# ADC_CH_B.net
KiCad netlist of a schematic drawn in Altium Designer
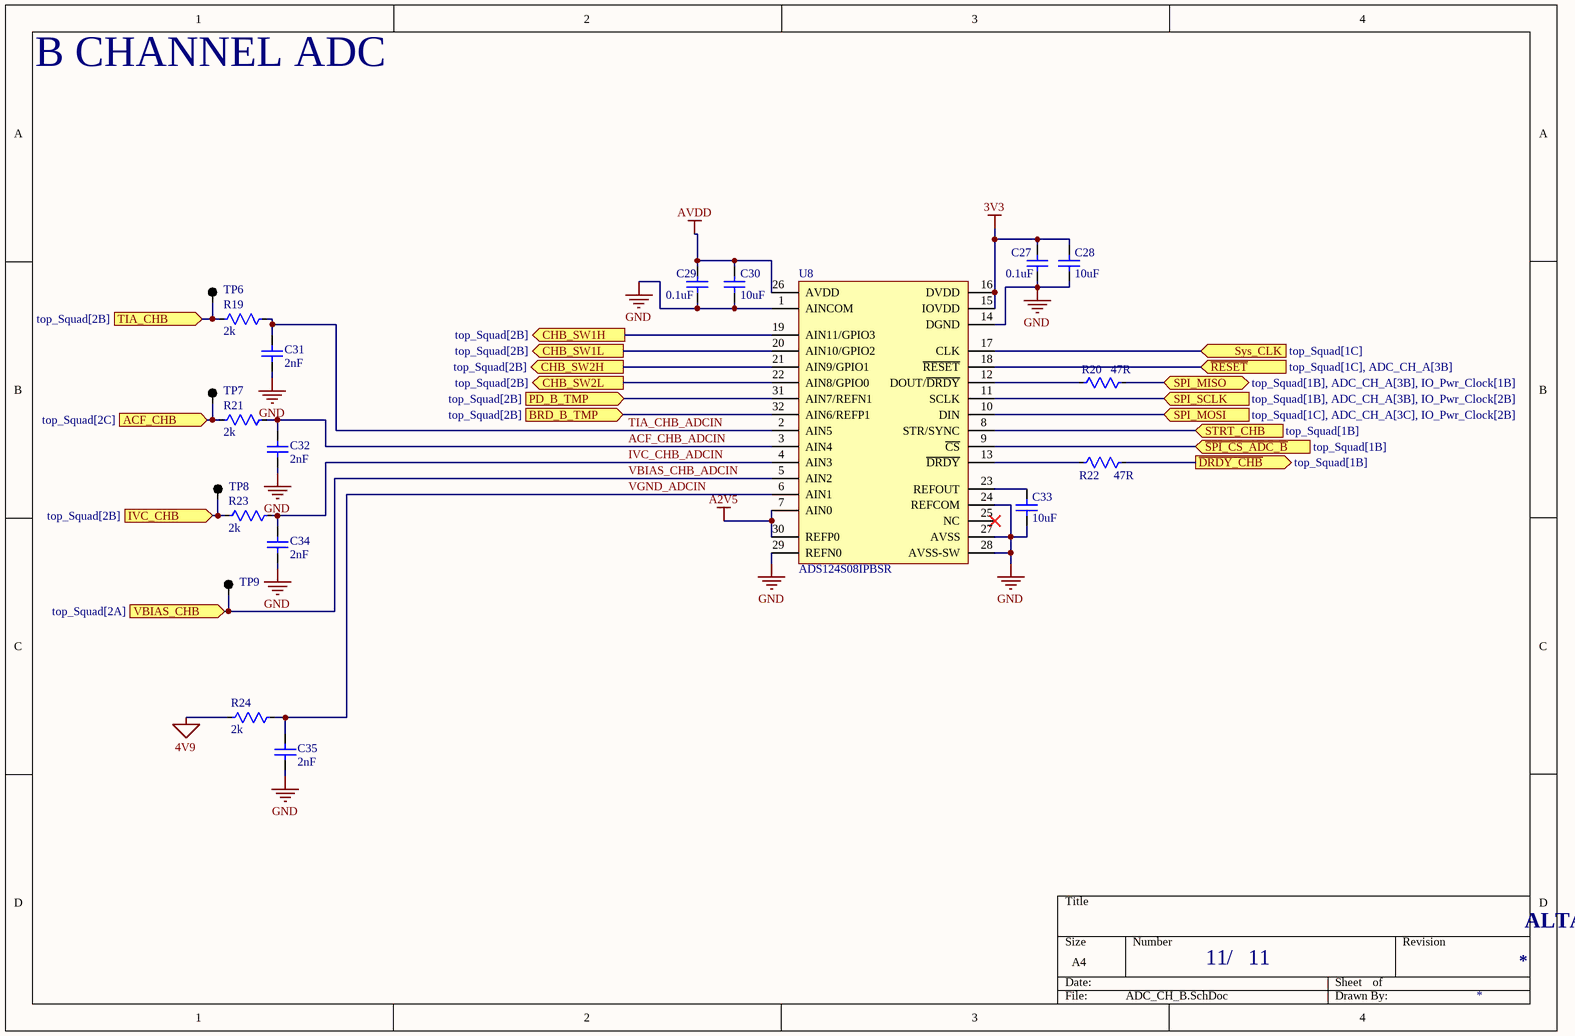
[diagram p0: ADC_CH_B.SchDoc]

(export (version "E")
  (design (tool "Eeschema 10.0.6"))
  (components
    (comp (ref "C27")
      (value "0.1uF")
      (footprint "CAP 0603 IPC MID DENSITY")
      (description "Kemet C0603C104K5RACAUTO - Cap Ceramic 0.1uF 50V X7R 10% 0603 125C Paper T/R")
      (fields (field (name "MF") "Kemet") (field (name "MP") "C0603C104K5RACAUTO"))
      (libsource (lib "ALTAIR_PD_Capacitors") (part "CAP"))
    )
    (comp (ref "C28")
      (value "10uF")
      (footprint "CAP 0805 IPC MID DENSITY")
      (description "Murata GRM21BR61E106KA73L - Cap Ceramic 10uF 10% 25V X5R 0805")
      (fields (field (name "MF") "Murata") (field (name "MP") "GRM21BR61E106KA73L"))
      (libsource (lib "ALTAIR_PD_Capacitors") (part "CAP"))
    )
    (comp (ref "C29")
      (value "0.1uF")
      (footprint "CAP 0603 IPC MID DENSITY")
      (description "Kemet C0603C104K5RACAUTO - Cap Ceramic 0.1uF 50V X7R 10% 0603 125C Paper T/R")
      (fields (field (name "MF") "Kemet") (field (name "MP") "C0603C104K5RACAUTO"))
      (libsource (lib "ALTAIR_PD_Capacitors") (part "CAP"))
    )
    (comp (ref "C30")
      (value "10uF")
      (footprint "CAP 0805 IPC MID DENSITY")
      (description "Murata GRM21BR61E106KA73L - Cap Ceramic 10uF 10% 25V X5R 0805")
      (fields (field (name "MF") "Murata") (field (name "MP") "GRM21BR61E106KA73L"))
      (libsource (lib "ALTAIR_PD_Capacitors") (part "CAP"))
    )
    (comp (ref "C31")
      (value "2nF")
      (footprint "CAP 0603 IPC MID DENSITY")
      (description "Murata GCM1885C1H202FA16J 50V 2nF C0G ±1% 0603")
      (fields (field (name "MF") "Murata") (field (name "MP") "GCM1885C1H202FA16J"))
      (libsource (lib "ALTAIR_PD_Capacitors") (part "CAP"))
    )
    (comp (ref "C32")
      (value "2nF")
      (footprint "CAP 0603 IPC MID DENSITY")
      (description "Murata GCM1885C1H202FA16J 50V 2nF C0G ±1% 0603")
      (fields (field (name "MF") "Murata") (field (name "MP") "GCM1885C1H202FA16J"))
      (libsource (lib "ALTAIR_PD_Capacitors") (part "CAP"))
    )
    (comp (ref "C33")
      (value "10uF")
      (footprint "CAP 0805 IPC MID DENSITY")
      (description "Murata GRM21BR61E106KA73L - Cap Ceramic 10uF 10% 25V X5R 0805")
      (fields (field (name "MF") "Murata") (field (name "MP") "GRM21BR61E106KA73L"))
      (libsource (lib "ALTAIR_PD_Capacitors") (part "CAP"))
    )
    (comp (ref "C34")
      (value "2nF")
      (footprint "CAP 0603 IPC MID DENSITY")
      (description "Murata GCM1885C1H202FA16J 50V 2nF C0G ±1% 0603")
      (fields (field (name "MF") "Murata") (field (name "MP") "GCM1885C1H202FA16J"))
      (libsource (lib "ALTAIR_PD_Capacitors") (part "CAP"))
    )
    (comp (ref "C35")
      (value "2nF")
      (footprint "CAP 0603 IPC MID DENSITY")
      (description "Murata GCM1885C1H202FA16J 50V 2nF C0G ±1% 0603")
      (fields (field (name "MF") "Murata") (field (name "MP") "GCM1885C1H202FA16J"))
      (libsource (lib "ALTAIR_PD_Capacitors") (part "CAP"))
    )
    (comp (ref "R19")
      (value "2k")
      (footprint "RES 0603 IPC MID DENSITY")
      (description "Panasonic ERJ-3EKF2001V Res Thick Film 0603 2K Ohm 1% 1/10W ±100ppm/°C")
      (fields (field (name "MF") "Panasonic Electronic Components") (field (name "MP") "ERJ-3EKF2001V"))
      (libsource (lib "ALTAIR_PD_Resistors") (part "RES"))
    )
    (comp (ref "R20")
      (value "47R")
      (footprint "RES 0402 NON-IPC SEI")
      (description "Stackpole RMCF0402JT47R0 - Res 47Ohm 5% 0.063W 0402 Thick Film AEC-Q200 compliant")
      (fields (field (name "MF") "Stackpole Electronics Inc.") (field (name "MP") "RMCF0402JT47R0"))
      (libsource (lib "ALTAIR_PD_Resistors") (part "RES"))
    )
    (comp (ref "R21")
      (value "2k")
      (footprint "RES 0603 IPC MID DENSITY")
      (description "Panasonic ERJ-3EKF2001V Res Thick Film 0603 2K Ohm 1% 1/10W ±100ppm/°C")
      (fields (field (name "MF") "Panasonic Electronic Components") (field (name "MP") "ERJ-3EKF2001V"))
      (libsource (lib "ALTAIR_PD_Resistors") (part "RES"))
    )
    (comp (ref "R22")
      (value "47R")
      (footprint "RES 0402 NON-IPC SEI")
      (description "Stackpole RMCF0402JT47R0 - Res 47Ohm 5% 0.063W 0402 Thick Film AEC-Q200 compliant")
      (fields (field (name "MF") "Stackpole Electronics Inc.") (field (name "MP") "RMCF0402JT47R0"))
      (libsource (lib "ALTAIR_PD_Resistors") (part "RES"))
    )
    (comp (ref "R23")
      (value "2k")
      (footprint "RES 0603 IPC MID DENSITY")
      (description "Panasonic ERJ-3EKF2001V Res Thick Film 0603 2K Ohm 1% 1/10W ±100ppm/°C")
      (fields (field (name "MF") "Panasonic Electronic Components") (field (name "MP") "ERJ-3EKF2001V"))
      (libsource (lib "ALTAIR_PD_Resistors") (part "RES"))
    )
    (comp (ref "R24")
      (value "2k")
      (footprint "RES 0603 IPC MID DENSITY")
      (description "Panasonic ERJ-3EKF2001V Res Thick Film 0603 2K Ohm 1% 1/10W ±100ppm/°C")
      (fields (field (name "MF") "Panasonic Electronic Components") (field (name "MP") "ERJ-3EKF2001V"))
      (libsource (lib "ALTAIR_PD_Resistors") (part "RES"))
    )
    (comp (ref "TP6")
      (value "Testpoint")
      (footprint "TESTPOINT THT")
      (libsource (lib "ALTAIR_PD_Testpoint") (part "Testpoint"))
    )
    (comp (ref "TP7")
      (value "Testpoint")
      (footprint "TESTPOINT THT")
      (libsource (lib "ALTAIR_PD_Testpoint") (part "Testpoint"))
    )
    (comp (ref "TP8")
      (value "Testpoint")
      (footprint "TESTPOINT THT")
      (libsource (lib "ALTAIR_PD_Testpoint") (part "Testpoint"))
    )
    (comp (ref "TP9")
      (value "Testpoint")
      (footprint "TESTPOINT THT")
      (libsource (lib "ALTAIR_PD_Testpoint") (part "Testpoint"))
    )
    (comp (ref "U8")
      (value "ADS124S08IPBSR")
      (footprint "32TQFP 7X7MM IPC LOW DENSITY")
      (description "24BIT ADC Delta-Sigma 4k samples/s PGA V-reference")
      (fields (field (name "MF") "Texas Instruments"))
      (libsource (lib "ALTAIR_PD_ADCs") (part "ADS124S08IPBSR"))
    )
  )
  (nets
    (net (code "1") (name "/ACF_CHB") (class "Default")
      (node (ref "R21") (pin "1") (pinfunction "1_1") (pintype "passive"))
      (node (ref "TP7") (pin "1") (pinfunction "1_1") (pintype "passive"))
    )
    (net (code "2") (name "/ACF_CHB_ADCIN") (class "Default")
      (node (ref "C32") (pin "2") (pinfunction "2_2") (pintype "passive"))
      (node (ref "R21") (pin "2") (pinfunction "2_2") (pintype "passive"))
      (node (ref "U8") (pin "3") (pinfunction "AIN4_3") (pintype "passive"))
    )
    (net (code "3") (name "/BRD_B_TMP") (class "Default")
      (node (ref "U8") (pin "32") (pinfunction "AIN6/REFP1_32") (pintype "passive"))
    )
    (net (code "4") (name "/CHB_SW1H") (class "Default")
      (node (ref "U8") (pin "19") (pinfunction "AIN11/GPIO3_19") (pintype "passive"))
    )
    (net (code "5") (name "/CHB_SW1L") (class "Default")
      (node (ref "U8") (pin "20") (pinfunction "AIN10/GPIO2_20") (pintype "passive"))
    )
    (net (code "6") (name "/CHB_SW2H") (class "Default")
      (node (ref "U8") (pin "21") (pinfunction "AIN9/GPIO1_21") (pintype "passive"))
    )
    (net (code "7") (name "/CHB_SW2L") (class "Default")
      (node (ref "U8") (pin "22") (pinfunction "AIN8/GPIO0_22") (pintype "passive"))
    )
    (net (code "8") (name "/DRDY_CHB") (class "Default")
      (node (ref "R22") (pin "2") (pinfunction "2_2") (pintype "passive"))
    )
    (net (code "9") (name "/IVC_CHB") (class "Default")
      (node (ref "R23") (pin "1") (pinfunction "1_1") (pintype "passive"))
      (node (ref "TP8") (pin "1") (pinfunction "1_1") (pintype "passive"))
    )
    (net (code "10") (name "/IVC_CHB_ADCIN") (class "Default")
      (node (ref "C34") (pin "2") (pinfunction "2_2") (pintype "passive"))
      (node (ref "R23") (pin "2") (pinfunction "2_2") (pintype "passive"))
      (node (ref "U8") (pin "4") (pinfunction "AIN3_4") (pintype "passive"))
    )
    (net (code "11") (name "/PD_B_TMP") (class "Default")
      (node (ref "U8") (pin "31") (pinfunction "AIN7/REFN1_31") (pintype "passive"))
    )
    (net (code "12") (name "/RESET") (class "Default")
      (node (ref "U8") (pin "18") (pinfunction "~{RESET}_18") (pintype "passive"))
    )
    (net (code "13") (name "/SPI_CS_ADC_B") (class "Default")
      (node (ref "U8") (pin "9") (pinfunction "~{CS}_9") (pintype "passive"))
    )
    (net (code "14") (name "/SPI_MISO") (class "Default")
      (node (ref "R20") (pin "2") (pinfunction "2_2") (pintype "passive"))
    )
    (net (code "15") (name "/SPI_MOSI") (class "Default")
      (node (ref "U8") (pin "10") (pinfunction "DIN_10") (pintype "passive"))
    )
    (net (code "16") (name "/SPI_SCLK") (class "Default")
      (node (ref "U8") (pin "11") (pinfunction "SCLK_11") (pintype "passive"))
    )
    (net (code "17") (name "/STRT_CHB") (class "Default")
      (node (ref "U8") (pin "8") (pinfunction "STR/SYNC_8") (pintype "passive"))
    )
    (net (code "18") (name "/Sys_CLK") (class "Default")
      (node (ref "U8") (pin "17") (pinfunction "CLK_17") (pintype "passive"))
    )
    (net (code "19") (name "/TIA_CHB") (class "Default")
      (node (ref "R19") (pin "1") (pinfunction "1_1") (pintype "passive"))
      (node (ref "TP6") (pin "1") (pinfunction "1_1") (pintype "passive"))
    )
    (net (code "20") (name "/TIA_CHB_ADCIN") (class "Default")
      (node (ref "C31") (pin "2") (pinfunction "2_2") (pintype "passive"))
      (node (ref "R19") (pin "2") (pinfunction "2_2") (pintype "passive"))
      (node (ref "U8") (pin "2") (pinfunction "AIN5_2") (pintype "passive"))
    )
    (net (code "21") (name "/VBIAS_CHB_ADCIN") (class "Default")
      (node (ref "TP9") (pin "1") (pinfunction "1_1") (pintype "passive"))
      (node (ref "U8") (pin "5") (pinfunction "AIN2_5") (pintype "passive"))
    )
    (net (code "22") (name "/VGND_ADCIN") (class "Default")
      (node (ref "C35") (pin "2") (pinfunction "2_2") (pintype "passive"))
      (node (ref "R24") (pin "2") (pinfunction "2_2") (pintype "passive"))
      (node (ref "U8") (pin "6") (pinfunction "AIN1_6") (pintype "passive"))
    )
    (net (code "23") (name "3V3") (class "Default")
      (node (ref "C27") (pin "2") (pinfunction "2_2") (pintype "passive"))
      (node (ref "C28") (pin "2") (pinfunction "2_2") (pintype "passive"))
      (node (ref "U8") (pin "15") (pinfunction "IOVDD_15") (pintype "passive"))
      (node (ref "U8") (pin "16") (pinfunction "DVDD_16") (pintype "passive"))
    )
    (net (code "24") (name "4V9") (class "Default")
      (node (ref "R24") (pin "1") (pinfunction "1_1") (pintype "passive"))
    )
    (net (code "25") (name "A2V5") (class "Default")
      (node (ref "U8") (pin "30") (pinfunction "REFP0_30") (pintype "passive"))
      (node (ref "U8") (pin "7") (pinfunction "AIN0_7") (pintype "passive"))
    )
    (net (code "26") (name "AVDD") (class "Default")
      (node (ref "C29") (pin "2") (pinfunction "2_2") (pintype "passive"))
      (node (ref "C30") (pin "2") (pinfunction "2_2") (pintype "passive"))
      (node (ref "U8") (pin "26") (pinfunction "AVDD_26") (pintype "passive"))
    )
    (net (code "27") (name "GND") (class "Default")
      (node (ref "C27") (pin "1") (pinfunction "1_1") (pintype "passive"))
      (node (ref "C28") (pin "1") (pinfunction "1_1") (pintype "passive"))
      (node (ref "C29") (pin "1") (pinfunction "1_1") (pintype "passive"))
      (node (ref "C30") (pin "1") (pinfunction "1_1") (pintype "passive"))
      (node (ref "C31") (pin "1") (pinfunction "1_1") (pintype "passive"))
      (node (ref "C32") (pin "1") (pinfunction "1_1") (pintype "passive"))
      (node (ref "C33") (pin "1") (pinfunction "1_1") (pintype "passive"))
      (node (ref "C34") (pin "1") (pinfunction "1_1") (pintype "passive"))
      (node (ref "C35") (pin "1") (pinfunction "1_1") (pintype "passive"))
      (node (ref "U8") (pin "1") (pinfunction "AINCOM_1") (pintype "passive"))
      (node (ref "U8") (pin "14") (pinfunction "DGND_14") (pintype "passive"))
      (node (ref "U8") (pin "24") (pinfunction "REFCOM_24") (pintype "passive"))
      (node (ref "U8") (pin "27") (pinfunction "AVSS_27") (pintype "passive"))
      (node (ref "U8") (pin "28") (pinfunction "AVSS-SW_28") (pintype "passive"))
      (node (ref "U8") (pin "29") (pinfunction "REFN0_29") (pintype "passive"))
    )
    (net (code "28") (name "Net-(U8-DOUT{slash}~{DRDY})") (class "Default")
      (node (ref "R20") (pin "1") (pinfunction "1_1") (pintype "passive"))
      (node (ref "U8") (pin "12") (pinfunction "DOUT/~{DRDY}_12") (pintype "passive"))
    )
    (net (code "29") (name "Net-(U8-REFOUT)") (class "Default")
      (node (ref "C33") (pin "2") (pinfunction "2_2") (pintype "passive"))
      (node (ref "U8") (pin "23") (pinfunction "REFOUT_23") (pintype "passive"))
    )
    (net (code "30") (name "Net-(U8-~{DRDY})") (class "Default")
      (node (ref "R22") (pin "1") (pinfunction "1_1") (pintype "passive"))
      (node (ref "U8") (pin "13") (pinfunction "~{DRDY}_13") (pintype "passive"))
    )
    (net (code "31") (name "unconnected-(U8-NC-Pad25)") (class "Default")
      (node (ref "U8") (pin "25") (pinfunction "NC_25") (pintype "passive+no_connect"))
    )
  )
)
